# Dcdc_12V0_16V5.net
KiCad netlist of a schematic drawn in Altium Designer
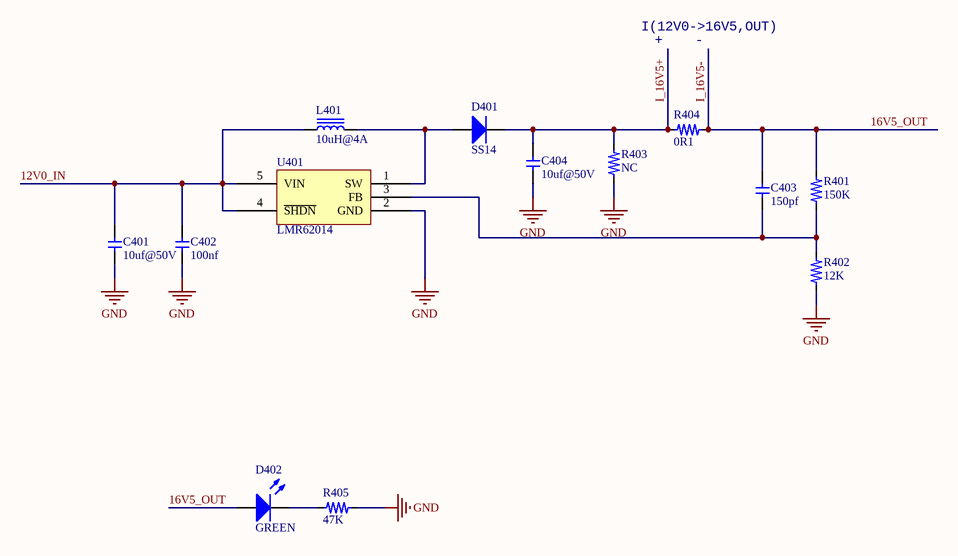
[diagram p0: Dcdc.12V0.+16V5.SchDoc]

(export (version "E")
  (design (tool "Eeschema 10.0.6"))
  (components
    (comp (ref "C401")
      (value "10uf@50V")
      (footprint "C1210")
      (fields (field (name "Comment") "Cap"))
      (libsource (lib "carrot_lib") (part "Cap"))
    )
    (comp (ref "C402")
      (value "100nf")
      (footprint "C0603")
      (fields (field (name "Comment") "Cap"))
      (libsource (lib "carrot_lib") (part "Cap"))
    )
    (comp (ref "C403")
      (value "150pf")
      (footprint "C0603")
      (fields (field (name "Comment") "Cap"))
      (libsource (lib "carrot_lib") (part "Cap"))
    )
    (comp (ref "C404")
      (value "10uf@50V")
      (footprint "C1210")
      (fields (field (name "Comment") "Cap"))
      (libsource (lib "carrot_lib") (part "Cap"))
    )
    (comp (ref "D401")
      (value "SS14")
      (footprint "DIODE-SMAF")
      (description "通用二极管")
      (fields (field (name "Comment") "Diode"))
      (libsource (lib "carrot_lib") (part "Diode"))
    )
    (comp (ref "D402")
      (value "GREEN")
      (footprint "LED0603")
      (fields (field (name "Comment") "LED"))
      (libsource (lib "carrot_lib") (part "LED"))
    )
    (comp (ref "L401")
      (value "10uH@4A")
      (footprint "L06063")
      (description "Magnetic-Core Inductor")
      (fields (field (name "Comment") "Inductor Iron"))
      (libsource (lib "carrot_lib") (part "Inductor Iron"))
    )
    (comp (ref "R401")
      (value "150K")
      (footprint "R0603")
      (description "电阻")
      (fields (field (name "Comment") "Res"))
      (libsource (lib "carrot_lib") (part "Res"))
    )
    (comp (ref "R402")
      (value "12K")
      (footprint "R0603")
      (description "电阻")
      (fields (field (name "Comment") "Res"))
      (libsource (lib "carrot_lib") (part "Res"))
    )
    (comp (ref "R403")
      (value "NC")
      (footprint "R1210")
      (description "电阻")
      (fields (field (name "Comment") "Res"))
      (libsource (lib "carrot_lib") (part "Res"))
    )
    (comp (ref "R404")
      (value "0R1")
      (footprint "R1206")
      (description "电阻")
      (fields (field (name "Comment") "Res"))
      (libsource (lib "carrot_lib") (part "Res"))
    )
    (comp (ref "R405")
      (value "47K")
      (footprint "R0603")
      (description "电阻")
      (fields (field (name "Comment") "Res"))
      (libsource (lib "carrot_lib") (part "Res"))
    )
    (comp (ref "U401")
      (value "LMR62014")
      (footprint "LMR62014-SOT23-5")
      (description "LMR62014 SIMPLE SWITCHER® 20Vout, 1.4A Step-Up Voltage Regulator in SOT-23")
      (libsource (lib "carrot_lib") (part "LMR62014"))
    )
  )
  (nets
    (net (code "1") (name "/12V0_IN") (class "Default")
      (node (ref "C401") (pin "2") (pinfunction "2_2") (pintype "passive"))
      (node (ref "C402") (pin "2") (pinfunction "2_2") (pintype "passive"))
      (node (ref "L401") (pin "1") (pinfunction "1_1") (pintype "passive"))
      (node (ref "U401") (pin "4") (pinfunction "~{SHDN}_4") (pintype "passive"))
      (node (ref "U401") (pin "5") (pinfunction "VIN_5") (pintype "passive"))
    )
    (net (code "2") (name "/16V5_OUT") (class "Default")
      (node (ref "C403") (pin "1") (pinfunction "1_1") (pintype "passive"))
      (node (ref "D402") (pin "1") (pinfunction "A_1") (pintype "passive"))
      (node (ref "R401") (pin "2") (pinfunction "2_2") (pintype "passive"))
      (node (ref "R404") (pin "2") (pinfunction "2_2") (pintype "passive"))
    )
    (net (code "3") (name "/I_16V5+") (class "Default")
      (node (ref "C404") (pin "2") (pinfunction "2_2") (pintype "passive"))
      (node (ref "D401") (pin "2") (pinfunction "K_2") (pintype "passive"))
      (node (ref "R403") (pin "2") (pinfunction "2_2") (pintype "passive"))
      (node (ref "R404") (pin "1") (pinfunction "1_1") (pintype "passive"))
    )
    (net (code "4") (name "GND") (class "Default")
      (node (ref "C401") (pin "1") (pinfunction "1_1") (pintype "passive"))
      (node (ref "C402") (pin "1") (pinfunction "1_1") (pintype "passive"))
      (node (ref "C404") (pin "1") (pinfunction "1_1") (pintype "passive"))
      (node (ref "R402") (pin "1") (pinfunction "1_1") (pintype "passive"))
      (node (ref "R403") (pin "1") (pinfunction "1_1") (pintype "passive"))
      (node (ref "R405") (pin "1") (pinfunction "1_1") (pintype "passive"))
      (node (ref "U401") (pin "2") (pinfunction "GND_2") (pintype "passive"))
    )
    (net (code "5") (name "Net-(D401-A)") (class "Default")
      (node (ref "D401") (pin "1") (pinfunction "A_1") (pintype "passive"))
      (node (ref "L401") (pin "2") (pinfunction "2_2") (pintype "passive"))
      (node (ref "U401") (pin "1") (pinfunction "SW_1") (pintype "passive"))
    )
    (net (code "6") (name "Net-(D402-K)") (class "Default")
      (node (ref "D402") (pin "2") (pinfunction "K_2") (pintype "passive"))
      (node (ref "R405") (pin "2") (pinfunction "2_2") (pintype "passive"))
    )
    (net (code "7") (name "Net-(U401-FB)") (class "Default")
      (node (ref "C403") (pin "2") (pinfunction "2_2") (pintype "passive"))
      (node (ref "R401") (pin "1") (pinfunction "1_1") (pintype "passive"))
      (node (ref "R402") (pin "2") (pinfunction "2_2") (pintype "passive"))
      (node (ref "U401") (pin "3") (pinfunction "FB_3") (pintype "passive"))
    )
  )
)
